# Uno.net
KiCad netlist of a schematic drawn in EAGLE
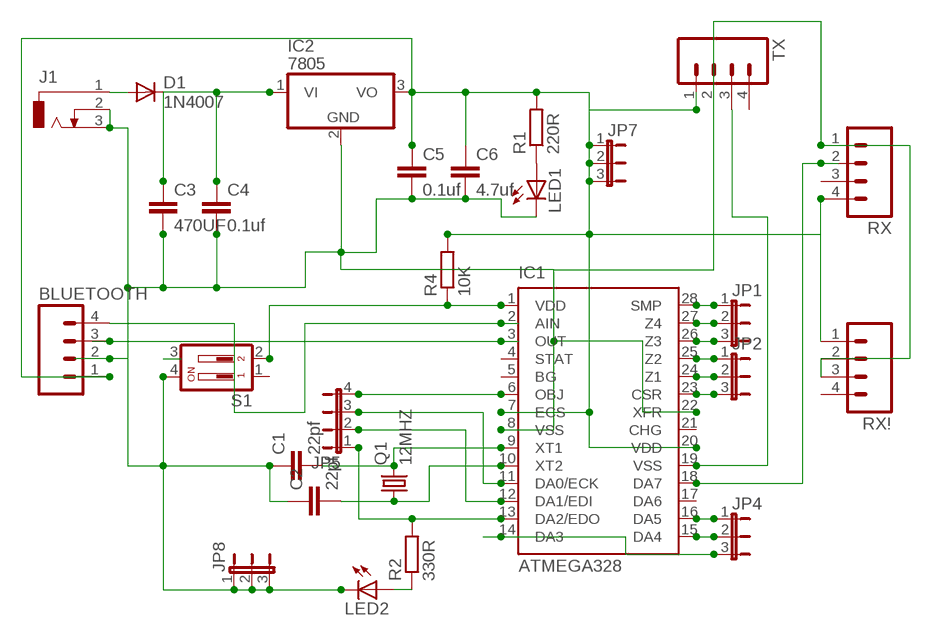
[diagram p0: schematic, sheet 1]

(export (version "E")
  (design (tool "Eeschema 10.0.6"))
  (components
    (comp (ref "BLUETOOTH")
      (value "M04")
      (footprint "eagle-import:04P")
      (libsource (lib "eagle-import") (part "M04"))
    )
    (comp (ref "C1")
      (value "22pf")
      (footprint "eagle-import:C2.5-2")
      (libsource (lib "eagle-import") (part "C2.5/2"))
    )
    (comp (ref "C2")
      (value "22pf")
      (footprint "eagle-import:C2.5-2")
      (libsource (lib "eagle-import") (part "C2.5/2"))
    )
    (comp (ref "C3")
      (value "470UF")
      (footprint "eagle-import:C2.5-2")
      (libsource (lib "eagle-import") (part "C2.5/2"))
    )
    (comp (ref "C4")
      (value "0.1uf")
      (footprint "eagle-import:C2.5-2")
      (libsource (lib "eagle-import") (part "C2.5/2"))
    )
    (comp (ref "C5")
      (value "0.1uf")
      (footprint "eagle-import:C2.5-2")
      (libsource (lib "eagle-import") (part "C2.5/2"))
    )
    (comp (ref "C6")
      (value "4.7uf")
      (footprint "eagle-import:C2.5-2")
      (libsource (lib "eagle-import") (part "C2.5/2"))
    )
    (comp (ref "D1")
      (value "1N4007")
      (footprint "eagle-import:DO41-10")
      (libsource (lib "eagle-import") (part "1N4004"))
    )
    (comp (ref "IC1")
      (value "ATMEGA328")
      (footprint "eagle-import:DIL28-3")
      (libsource (lib "eagle-import") (part "QT9701BD"))
    )
    (comp (ref "IC2")
      (value "7805")
      (footprint "eagle-import:TO220V")
      (libsource (lib "eagle-import") (part "78TV6"))
    )
    (comp (ref "J1")
      (value "DCJ0303")
      (footprint "eagle-import:DCJ0303")
      (libsource (lib "eagle-import") (part "DCJ0303"))
    )
    (comp (ref "JP1")
      (value "JP2E")
      (footprint "eagle-import:JP2")
      (libsource (lib "eagle-import") (part "JP2E"))
    )
    (comp (ref "JP2")
      (value "JP2E")
      (footprint "eagle-import:JP2")
      (libsource (lib "eagle-import") (part "JP2E"))
    )
    (comp (ref "JP4")
      (value "JP2E")
      (footprint "eagle-import:JP2")
      (libsource (lib "eagle-import") (part "JP2E"))
    )
    (comp (ref "JP5")
      (value "JP4E")
      (footprint "eagle-import:JP4")
      (libsource (lib "eagle-import") (part "JP4E"))
    )
    (comp (ref "JP7")
      (value "JP2E")
      (footprint "eagle-import:JP2")
      (libsource (lib "eagle-import") (part "JP2E"))
    )
    (comp (ref "JP8")
      (value "JP2E")
      (footprint "eagle-import:JP2")
      (libsource (lib "eagle-import") (part "JP2E"))
    )
    (comp (ref "LED1")
      (value "LED3MM")
      (footprint "eagle-import:LED3MM")
      (libsource (lib "eagle-import") (part "LED3MM"))
    )
    (comp (ref "LED2")
      (value "LED3MM")
      (footprint "eagle-import:LED3MM")
      (libsource (lib "eagle-import") (part "LED3MM"))
    )
    (comp (ref "Q1")
      (value "12MHZ")
      (footprint "eagle-import:HC49_S")
      (libsource (lib "eagle-import") (part "CRYSTALHC49S"))
    )
    (comp (ref "R1")
      (value "220R")
      (footprint "eagle-import:0207_10")
      (libsource (lib "eagle-import") (part "R-EU_0207/10"))
    )
    (comp (ref "R2")
      (value "330R")
      (footprint "eagle-import:0207_10")
      (libsource (lib "eagle-import") (part "R-EU_0207/10"))
    )
    (comp (ref "R4")
      (value "10K")
      (footprint "eagle-import:0207_10")
      (libsource (lib "eagle-import") (part "R-EU_0207/10"))
    )
    (comp (ref "RX")
      (value "M04")
      (footprint "eagle-import:04P")
      (libsource (lib "eagle-import") (part "M04"))
    )
    (comp (ref "RX!")
      (value "M04")
      (footprint "eagle-import:04P")
      (libsource (lib "eagle-import") (part "M04"))
    )
    (comp (ref "S1")
      (value "DP02")
      (footprint "eagle-import:DP-02")
      (fields (field (name "MPN") "MCDP02"))
      (libsource (lib "eagle-import") (part "DP02"))
    )
    (comp (ref "TX")
      (value "M04")
      (footprint "eagle-import:04P")
      (libsource (lib "eagle-import") (part "M04"))
    )
  )
  (nets
    (net (code "1") (name "Net-(D1-PadA)") (class "Default")
      (node (ref "D1") (pin "A") (pinfunction "A_A") (pintype "passive"))
      (node (ref "J1") (pin "1") (pinfunction "1_1") (pintype "passive"))
    )
    (net (code "2") (name "Net-(IC1-AIN)") (class "Default")
      (node (ref "BLUETOOTH") (pin "4") (pinfunction "4_4") (pintype "passive"))
      (node (ref "IC1") (pin "2") (pinfunction "AIN_2") (pintype "input"))
    )
    (net (code "3") (name "Net-(IC1-CSR)") (class "Default")
      (node (ref "IC1") (pin "23") (pinfunction "CSR_23") (pintype "output"))
      (node (ref "JP2") (pin "3") (pinfunction "3_3") (pintype "passive"))
    )
    (net (code "4") (name "Net-(IC1-DA0{slash}ECK)") (class "Default")
      (node (ref "IC1") (pin "11") (pinfunction "DA0/ECK_11") (pintype "output"))
      (node (ref "JP5") (pin "3") (pinfunction "3_3") (pintype "passive"))
    )
    (net (code "5") (name "Net-(IC1-DA1{slash}EDI)") (class "Default")
      (node (ref "IC1") (pin "12") (pinfunction "DA1/EDI_12") (pintype "output"))
      (node (ref "JP5") (pin "2") (pinfunction "2_2") (pintype "passive"))
    )
    (net (code "6") (name "Net-(IC1-DA2{slash}EDO)") (class "Default")
      (node (ref "IC1") (pin "13") (pinfunction "DA2/EDO_13") (pintype "output"))
      (node (ref "JP5") (pin "1") (pinfunction "1_1") (pintype "passive"))
      (node (ref "R2") (pin "2") (pinfunction "2_2") (pintype "passive"))
    )
    (net (code "7") (name "Net-(IC1-DA3)") (class "Default")
      (node (ref "IC1") (pin "14") (pinfunction "DA3_14") (pintype "output"))
      (node (ref "JP4") (pin "3") (pinfunction "3_3") (pintype "passive"))
    )
    (net (code "8") (name "Net-(IC1-DA4)") (class "Default")
      (node (ref "IC1") (pin "15") (pinfunction "DA4_15") (pintype "output"))
      (node (ref "JP4") (pin "2") (pinfunction "2_2") (pintype "passive"))
    )
    (net (code "9") (name "Net-(IC1-DA5)") (class "Default")
      (node (ref "IC1") (pin "16") (pinfunction "DA5_16") (pintype "output"))
      (node (ref "JP4") (pin "1") (pinfunction "1_1") (pintype "passive"))
    )
    (net (code "10") (name "Net-(IC1-DA7)") (class "Default")
      (node (ref "IC1") (pin "18") (pinfunction "DA7_18") (pintype "output"))
      (node (ref "RX") (pin "2") (pinfunction "2_2") (pintype "passive"))
    )
    (net (code "11") (name "Net-(IC1-ECS)") (class "Default")
      (node (ref "BLUETOOTH") (pin "1") (pinfunction "1_1") (pintype "passive"))
      (node (ref "C5") (pin "1") (pinfunction "1_1") (pintype "passive"))
      (node (ref "C6") (pin "1") (pinfunction "1_1") (pintype "passive"))
      (node (ref "IC1") (pin "20") (pinfunction "VDD_20") (pintype "input"))
      (node (ref "IC1") (pin "7") (pinfunction "ECS_7") (pintype "output"))
      (node (ref "IC2") (pin "3") (pinfunction "VO_3") (pintype "passive"))
      (node (ref "JP7") (pin "1") (pinfunction "1_1") (pintype "passive"))
      (node (ref "JP7") (pin "2") (pinfunction "2_2") (pintype "passive"))
      (node (ref "JP7") (pin "3") (pinfunction "3_3") (pintype "passive"))
      (node (ref "R1") (pin "2") (pinfunction "2_2") (pintype "passive"))
      (node (ref "R4") (pin "2") (pinfunction "2_2") (pintype "passive"))
      (node (ref "RX") (pin "4") (pinfunction "4_4") (pintype "passive"))
      (node (ref "RX!") (pin "1") (pinfunction "1_1") (pintype "passive"))
      (node (ref "TX") (pin "1") (pinfunction "1_1") (pintype "passive"))
    )
    (net (code "12") (name "Net-(IC1-OBJ)") (class "Default")
      (node (ref "IC1") (pin "6") (pinfunction "OBJ_6") (pintype "input"))
      (node (ref "JP5") (pin "4") (pinfunction "4_4") (pintype "passive"))
    )
    (net (code "13") (name "Net-(IC1-OUT)") (class "Default")
      (node (ref "BLUETOOTH") (pin "3") (pinfunction "3_3") (pintype "passive"))
      (node (ref "IC1") (pin "3") (pinfunction "OUT_3") (pintype "output"))
    )
    (net (code "14") (name "Net-(IC1-SMP)") (class "Default")
      (node (ref "IC1") (pin "28") (pinfunction "SMP_28") (pintype "output"))
      (node (ref "JP1") (pin "1") (pinfunction "1_1") (pintype "passive"))
    )
    (net (code "15") (name "Net-(IC1-VDD-Pad1)") (class "Default")
      (node (ref "IC1") (pin "1") (pinfunction "VDD_1") (pintype "input"))
      (node (ref "R4") (pin "1") (pinfunction "1_1") (pintype "passive"))
      (node (ref "S1") (pin "2") (pinfunction "2_2") (pintype "passive"))
    )
    (net (code "16") (name "Net-(IC1-VSS-Pad19)") (class "Default")
      (node (ref "IC1") (pin "19") (pinfunction "VSS_19") (pintype "input"))
      (node (ref "TX") (pin "3") (pinfunction "3_3") (pintype "passive"))
    )
    (net (code "17") (name "Net-(IC1-XFR)") (class "Default")
      (node (ref "BLUETOOTH") (pin "2") (pinfunction "2_2") (pintype "passive"))
      (node (ref "C1") (pin "1") (pinfunction "1_1") (pintype "passive"))
      (node (ref "C2") (pin "1") (pinfunction "1_1") (pintype "passive"))
      (node (ref "C3") (pin "2") (pinfunction "2_2") (pintype "passive"))
      (node (ref "C4") (pin "2") (pinfunction "2_2") (pintype "passive"))
      (node (ref "C5") (pin "2") (pinfunction "2_2") (pintype "passive"))
      (node (ref "C6") (pin "2") (pinfunction "2_2") (pintype "passive"))
      (node (ref "IC1") (pin "22") (pinfunction "XFR_22") (pintype "output"))
      (node (ref "IC1") (pin "8") (pinfunction "VSS_8") (pintype "input"))
      (node (ref "IC2") (pin "2") (pinfunction "GND_2") (pintype "passive"))
      (node (ref "J1") (pin "2") (pinfunction "2_2") (pintype "passive"))
      (node (ref "J1") (pin "3") (pinfunction "3_3") (pintype "passive"))
      (node (ref "JP8") (pin "1") (pinfunction "1_1") (pintype "passive"))
      (node (ref "JP8") (pin "2") (pinfunction "2_2") (pintype "passive"))
      (node (ref "JP8") (pin "3") (pinfunction "3_3") (pintype "passive"))
      (node (ref "LED1") (pin "K") (pinfunction "C_K") (pintype "passive"))
      (node (ref "LED2") (pin "K") (pinfunction "C_K") (pintype "passive"))
      (node (ref "RX") (pin "1") (pinfunction "1_1") (pintype "passive"))
      (node (ref "RX!") (pin "2") (pinfunction "2_2") (pintype "passive"))
      (node (ref "RX!") (pin "3") (pinfunction "3_3") (pintype "passive"))
      (node (ref "S1") (pin "4") (pinfunction "4_4") (pintype "passive"))
      (node (ref "TX") (pin "2") (pinfunction "2_2") (pintype "passive"))
    )
    (net (code "18") (name "Net-(IC1-XT1)") (class "Default")
      (node (ref "C1") (pin "2") (pinfunction "2_2") (pintype "passive"))
      (node (ref "IC1") (pin "9") (pinfunction "XT1_9") (pintype "input"))
      (node (ref "Q1") (pin "2") (pinfunction "2_2") (pintype "passive"))
    )
    (net (code "19") (name "Net-(IC1-XT2)") (class "Default")
      (node (ref "C2") (pin "2") (pinfunction "2_2") (pintype "passive"))
      (node (ref "IC1") (pin "10") (pinfunction "XT2_10") (pintype "output"))
      (node (ref "Q1") (pin "1") (pinfunction "1_1") (pintype "passive"))
    )
    (net (code "20") (name "Net-(IC1-Z1)") (class "Default")
      (node (ref "IC1") (pin "24") (pinfunction "Z1_24") (pintype "output"))
      (node (ref "JP2") (pin "2") (pinfunction "2_2") (pintype "passive"))
    )
    (net (code "21") (name "Net-(IC1-Z2)") (class "Default")
      (node (ref "IC1") (pin "25") (pinfunction "Z2_25") (pintype "output"))
      (node (ref "JP2") (pin "1") (pinfunction "1_1") (pintype "passive"))
    )
    (net (code "22") (name "Net-(IC1-Z3)") (class "Default")
      (node (ref "IC1") (pin "26") (pinfunction "Z3_26") (pintype "output"))
      (node (ref "JP1") (pin "3") (pinfunction "3_3") (pintype "passive"))
    )
    (net (code "23") (name "Net-(IC1-Z4)") (class "Default")
      (node (ref "IC1") (pin "27") (pinfunction "Z4_27") (pintype "output"))
      (node (ref "JP1") (pin "2") (pinfunction "2_2") (pintype "passive"))
    )
    (net (code "24") (name "Net-(IC2-VI)") (class "Default")
      (node (ref "C3") (pin "1") (pinfunction "1_1") (pintype "passive"))
      (node (ref "C4") (pin "1") (pinfunction "1_1") (pintype "passive"))
      (node (ref "D1") (pin "C") (pinfunction "C_C") (pintype "passive"))
      (node (ref "IC2") (pin "1") (pinfunction "VI_1") (pintype "input"))
    )
    (net (code "25") (name "Net-(LED1-PadA)") (class "Default")
      (node (ref "LED1") (pin "A") (pinfunction "A_A") (pintype "passive"))
      (node (ref "R1") (pin "1") (pinfunction "1_1") (pintype "passive"))
    )
    (net (code "26") (name "Net-(LED2-PadA)") (class "Default")
      (node (ref "LED2") (pin "A") (pinfunction "A_A") (pintype "passive"))
      (node (ref "R2") (pin "1") (pinfunction "1_1") (pintype "passive"))
    )
    (net (code "27") (name "unconnected-(IC1-BG-Pad5)") (class "Default")
      (node (ref "IC1") (pin "5") (pinfunction "BG_5") (pintype "input"))
    )
    (net (code "28") (name "unconnected-(IC1-CHG-Pad21)") (class "Default")
      (node (ref "IC1") (pin "21") (pinfunction "CHG_21") (pintype "output"))
    )
    (net (code "29") (name "unconnected-(IC1-DA6-Pad17)") (class "Default")
      (node (ref "IC1") (pin "17") (pinfunction "DA6_17") (pintype "output"))
    )
    (net (code "30") (name "unconnected-(IC1-STAT-Pad4)") (class "Default")
      (node (ref "IC1") (pin "4") (pinfunction "STAT_4") (pintype "output"))
    )
    (net (code "31") (name "unconnected-(RX!-Pad4)") (class "Default")
      (node (ref "RX!") (pin "4") (pinfunction "4_4") (pintype "passive"))
    )
    (net (code "32") (name "unconnected-(RX-Pad3)") (class "Default")
      (node (ref "RX") (pin "3") (pinfunction "3_3") (pintype "passive"))
    )
    (net (code "33") (name "unconnected-(S1-Pad1)") (class "Default")
      (node (ref "S1") (pin "1") (pinfunction "1_1") (pintype "passive"))
    )
    (net (code "34") (name "unconnected-(S1-Pad3)") (class "Default")
      (node (ref "S1") (pin "3") (pinfunction "3_3") (pintype "passive"))
    )
    (net (code "35") (name "unconnected-(TX-Pad4)") (class "Default")
      (node (ref "TX") (pin "4") (pinfunction "4_4") (pintype "passive"))
    )
  )
)
